# MHI-AC-Ctrl_v1_2.net
KiCad netlist of a schematic drawn in EAGLE
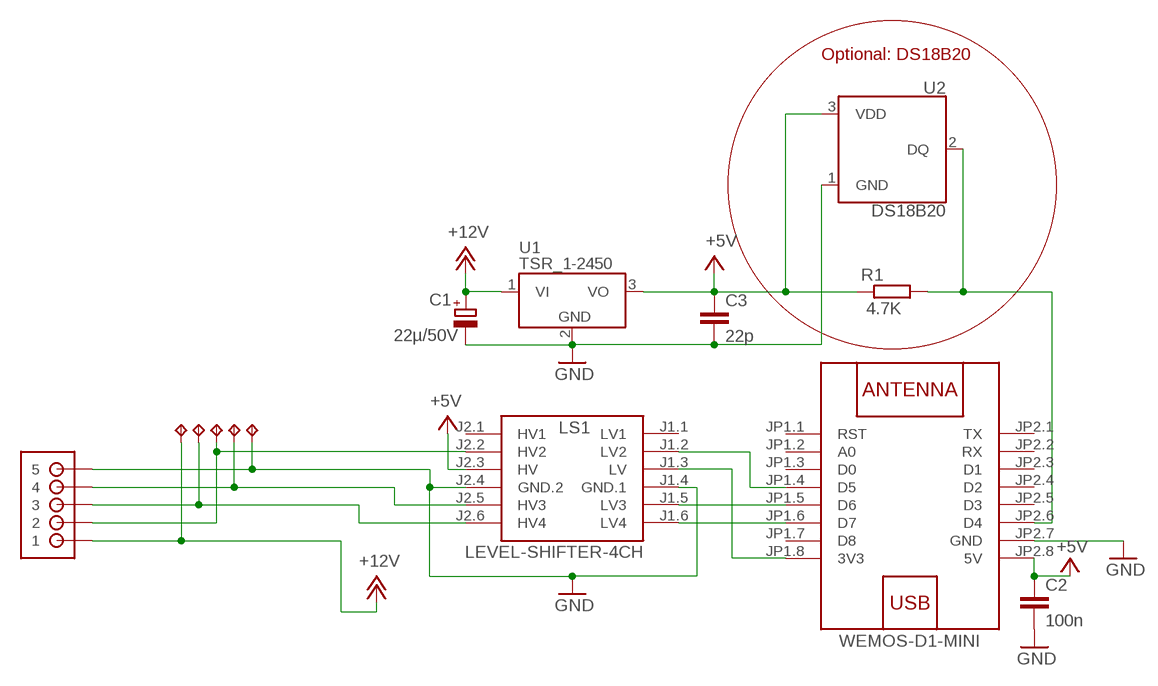
[diagram p0: schematic, sheet 1]

(export (version "E")
  (design (tool "Eeschema 10.0.6"))
  (components
    (comp (ref "C1")
      (value "22µ/50V")
      (footprint "eagle-import:E5-10,5")
      (libsource (lib "eagle-import") (part "CPOL-EUE5-10.5"))
    )
    (comp (ref "C2")
      (value "100n")
      (footprint "eagle-import:C025-024X044")
      (libsource (lib "eagle-import") (part "C-EU025-024X044"))
    )
    (comp (ref "C3")
      (value "22p")
      (footprint "eagle-import:C025-024X044")
      (libsource (lib "eagle-import") (part "C-EU025-024X044"))
    )
    (comp (ref "LS1")
      (value "LEVEL-SHIFTER-4CH")
      (footprint "eagle-import:LEVEL-SHIFTER-4CH")
      (libsource (lib "eagle-import") (part "LEVEL-SHIFTER-4CH"))
    )
    (comp (ref "R1")
      (value "4.7K")
      (footprint "eagle-import:0204_7")
      (libsource (lib "eagle-import") (part "R-EU_0204/7"))
    )
    (comp (ref "TP9")
      (value "TPPAD1-13")
      (footprint "eagle-import:P1-13")
      (libsource (lib "eagle-import") (part "TPPAD1-13"))
    )
    (comp (ref "TP10")
      (value "TPPAD1-13")
      (footprint "eagle-import:P1-13")
      (libsource (lib "eagle-import") (part "TPPAD1-13"))
    )
    (comp (ref "TP11")
      (value "TPPAD1-13")
      (footprint "eagle-import:P1-13")
      (libsource (lib "eagle-import") (part "TPPAD1-13"))
    )
    (comp (ref "TP12")
      (value "TPPAD1-13")
      (footprint "eagle-import:P1-13")
      (libsource (lib "eagle-import") (part "TPPAD1-13"))
    )
    (comp (ref "TP13")
      (value "TPPAD1-13")
      (footprint "eagle-import:P1-13")
      (libsource (lib "eagle-import") (part "TPPAD1-13"))
    )
    (comp (ref "U$1")
      (value "WEMOS-D1-MINI")
      (footprint "eagle-import:WEMOS-D1-MINI")
      (libsource (lib "eagle-import") (part "WEMOS-D1-MINI"))
    )
    (comp (ref "U$4")
      (value "JST-PH_5-PIN_HEADER")
      (footprint "eagle-import:JST_B5B-PH_HEADER")
      (libsource (lib "eagle-import") (part "JST-PH_5-PIN_HEADER"))
    )
    (comp (ref "U1")
      (value "TSR_1-2450")
      (footprint "eagle-import:TSR-1")
      (libsource (lib "eagle-import") (part "TSR_1-24_"))
    )
    (comp (ref "U2")
      (value "DS18B20")
      (footprint "eagle-import:TO-92-TO92127P495H2044-3")
      (fields (field (name "MF") "Maxim Integrated"))
      (libsource (lib "eagle-import") (part "DS18B20"))
    )
  )
  (nets
    (net (code "1") (name "+5V") (class "Default")
      (node (ref "C2") (pin "1") (pinfunction "1_1") (pintype "passive"))
      (node (ref "C3") (pin "1") (pinfunction "1_1") (pintype "passive"))
      (node (ref "LS1") (pin "J2.3") (pinfunction "HV_J2.3") (pintype "power_in"))
      (node (ref "R1") (pin "2") (pinfunction "2_2") (pintype "passive"))
      (node (ref "U$1") (pin "JP2.8") (pinfunction "5V_JP2.8") (pintype "power_in"))
      (node (ref "U1") (pin "3") (pinfunction "VO_3") (pintype "power_in"))
      (node (ref "U2") (pin "3") (pinfunction "VDD_3") (pintype "power_in"))
    )
    (net (code "2") (name "+12V") (class "Default")
      (node (ref "C1") (pin "+") (pinfunction "+_+") (pintype "passive"))
      (node (ref "TP13") (pin "TP") (pinfunction "TP_TP") (pintype "input"))
      (node (ref "U$4") (pin "P1") (pinfunction "1_P1") (pintype "bidirectional"))
      (node (ref "U1") (pin "1") (pinfunction "VI_1") (pintype "power_in"))
    )
    (net (code "3") (name "GND") (class "Default")
      (node (ref "C1") (pin "-") (pinfunction "-_-") (pintype "passive"))
      (node (ref "C2") (pin "2") (pinfunction "2_2") (pintype "passive"))
      (node (ref "C3") (pin "2") (pinfunction "2_2") (pintype "passive"))
      (node (ref "LS1") (pin "J1.4") (pinfunction "GND.1_J1.4") (pintype "power_in"))
      (node (ref "LS1") (pin "J2.4") (pinfunction "GND.2_J2.4") (pintype "power_in"))
      (node (ref "TP9") (pin "TP") (pinfunction "TP_TP") (pintype "input"))
      (node (ref "U$1") (pin "JP2.7") (pinfunction "GND_JP2.7") (pintype "power_in"))
      (node (ref "U$4") (pin "P5") (pinfunction "5_P5") (pintype "bidirectional"))
      (node (ref "U1") (pin "2") (pinfunction "GND_2") (pintype "power_in"))
      (node (ref "U2") (pin "1") (pinfunction "GND_1") (pintype "power_in"))
    )
    (net (code "4") (name "Net-(LS1-HV2)") (class "Default")
      (node (ref "LS1") (pin "J2.2") (pinfunction "HV2_J2.2") (pintype "bidirectional"))
      (node (ref "TP11") (pin "TP") (pinfunction "TP_TP") (pintype "input"))
      (node (ref "U$4") (pin "P2") (pinfunction "2_P2") (pintype "bidirectional"))
    )
    (net (code "5") (name "Net-(LS1-HV3)") (class "Default")
      (node (ref "LS1") (pin "J2.5") (pinfunction "HV3_J2.5") (pintype "bidirectional"))
      (node (ref "TP10") (pin "TP") (pinfunction "TP_TP") (pintype "input"))
      (node (ref "U$4") (pin "P4") (pinfunction "4_P4") (pintype "bidirectional"))
    )
    (net (code "6") (name "Net-(LS1-HV4)") (class "Default")
      (node (ref "LS1") (pin "J2.6") (pinfunction "HV4_J2.6") (pintype "bidirectional"))
      (node (ref "TP12") (pin "TP") (pinfunction "TP_TP") (pintype "input"))
      (node (ref "U$4") (pin "P3") (pinfunction "3_P3") (pintype "bidirectional"))
    )
    (net (code "7") (name "Net-(LS1-LV)") (class "Default")
      (node (ref "LS1") (pin "J1.3") (pinfunction "LV_J1.3") (pintype "power_in"))
      (node (ref "U$1") (pin "JP1.8") (pinfunction "3V3_JP1.8") (pintype "power_in"))
    )
    (net (code "8") (name "Net-(LS1-LV2)") (class "Default")
      (node (ref "LS1") (pin "J1.2") (pinfunction "LV2_J1.2") (pintype "bidirectional"))
      (node (ref "U$1") (pin "JP1.4") (pinfunction "D5_JP1.4") (pintype "bidirectional"))
    )
    (net (code "9") (name "Net-(LS1-LV3)") (class "Default")
      (node (ref "LS1") (pin "J1.5") (pinfunction "LV3_J1.5") (pintype "bidirectional"))
      (node (ref "U$1") (pin "JP1.5") (pinfunction "D6_JP1.5") (pintype "bidirectional"))
    )
    (net (code "10") (name "Net-(LS1-LV4)") (class "Default")
      (node (ref "LS1") (pin "J1.6") (pinfunction "LV4_J1.6") (pintype "bidirectional"))
      (node (ref "U$1") (pin "JP1.6") (pinfunction "D7_JP1.6") (pintype "bidirectional"))
    )
    (net (code "11") (name "Net-(U$1-D4)") (class "Default")
      (node (ref "R1") (pin "1") (pinfunction "1_1") (pintype "passive"))
      (node (ref "U$1") (pin "JP2.6") (pinfunction "D4_JP2.6") (pintype "bidirectional"))
      (node (ref "U2") (pin "2") (pinfunction "DQ_2") (pintype "bidirectional"))
    )
    (net (code "12") (name "unconnected-(LS1-HV1-PadJ2.1)") (class "Default")
      (node (ref "LS1") (pin "J2.1") (pinfunction "HV1_J2.1") (pintype "bidirectional"))
    )
    (net (code "13") (name "unconnected-(LS1-LV1-PadJ1.1)") (class "Default")
      (node (ref "LS1") (pin "J1.1") (pinfunction "LV1_J1.1") (pintype "bidirectional"))
    )
    (net (code "14") (name "unconnected-(U$1-A0-PadJP1.2)") (class "Default")
      (node (ref "U$1") (pin "JP1.2") (pinfunction "A0_JP1.2") (pintype "bidirectional"))
    )
    (net (code "15") (name "unconnected-(U$1-D0-PadJP1.3)") (class "Default")
      (node (ref "U$1") (pin "JP1.3") (pinfunction "D0_JP1.3") (pintype "bidirectional"))
    )
    (net (code "16") (name "unconnected-(U$1-D1-PadJP2.3)") (class "Default")
      (node (ref "U$1") (pin "JP2.3") (pinfunction "D1_JP2.3") (pintype "bidirectional"))
    )
    (net (code "17") (name "unconnected-(U$1-D2-PadJP2.4)") (class "Default")
      (node (ref "U$1") (pin "JP2.4") (pinfunction "D2_JP2.4") (pintype "bidirectional"))
    )
    (net (code "18") (name "unconnected-(U$1-D3-PadJP2.5)") (class "Default")
      (node (ref "U$1") (pin "JP2.5") (pinfunction "D3_JP2.5") (pintype "bidirectional"))
    )
    (net (code "19") (name "unconnected-(U$1-D8-PadJP1.7)") (class "Default")
      (node (ref "U$1") (pin "JP1.7") (pinfunction "D8_JP1.7") (pintype "bidirectional"))
    )
    (net (code "20") (name "unconnected-(U$1-RST-PadJP1.1)") (class "Default")
      (node (ref "U$1") (pin "JP1.1") (pinfunction "RST_JP1.1") (pintype "bidirectional"))
    )
    (net (code "21") (name "unconnected-(U$1-RX-PadJP2.2)") (class "Default")
      (node (ref "U$1") (pin "JP2.2") (pinfunction "RX_JP2.2") (pintype "bidirectional"))
    )
    (net (code "22") (name "unconnected-(U$1-TX-PadJP2.1)") (class "Default")
      (node (ref "U$1") (pin "JP2.1") (pinfunction "TX_JP2.1") (pintype "bidirectional"))
    )
  )
)
